# MinieasySens-RFM_V03-Build007.net
KiCad netlist of a schematic drawn in EAGLE
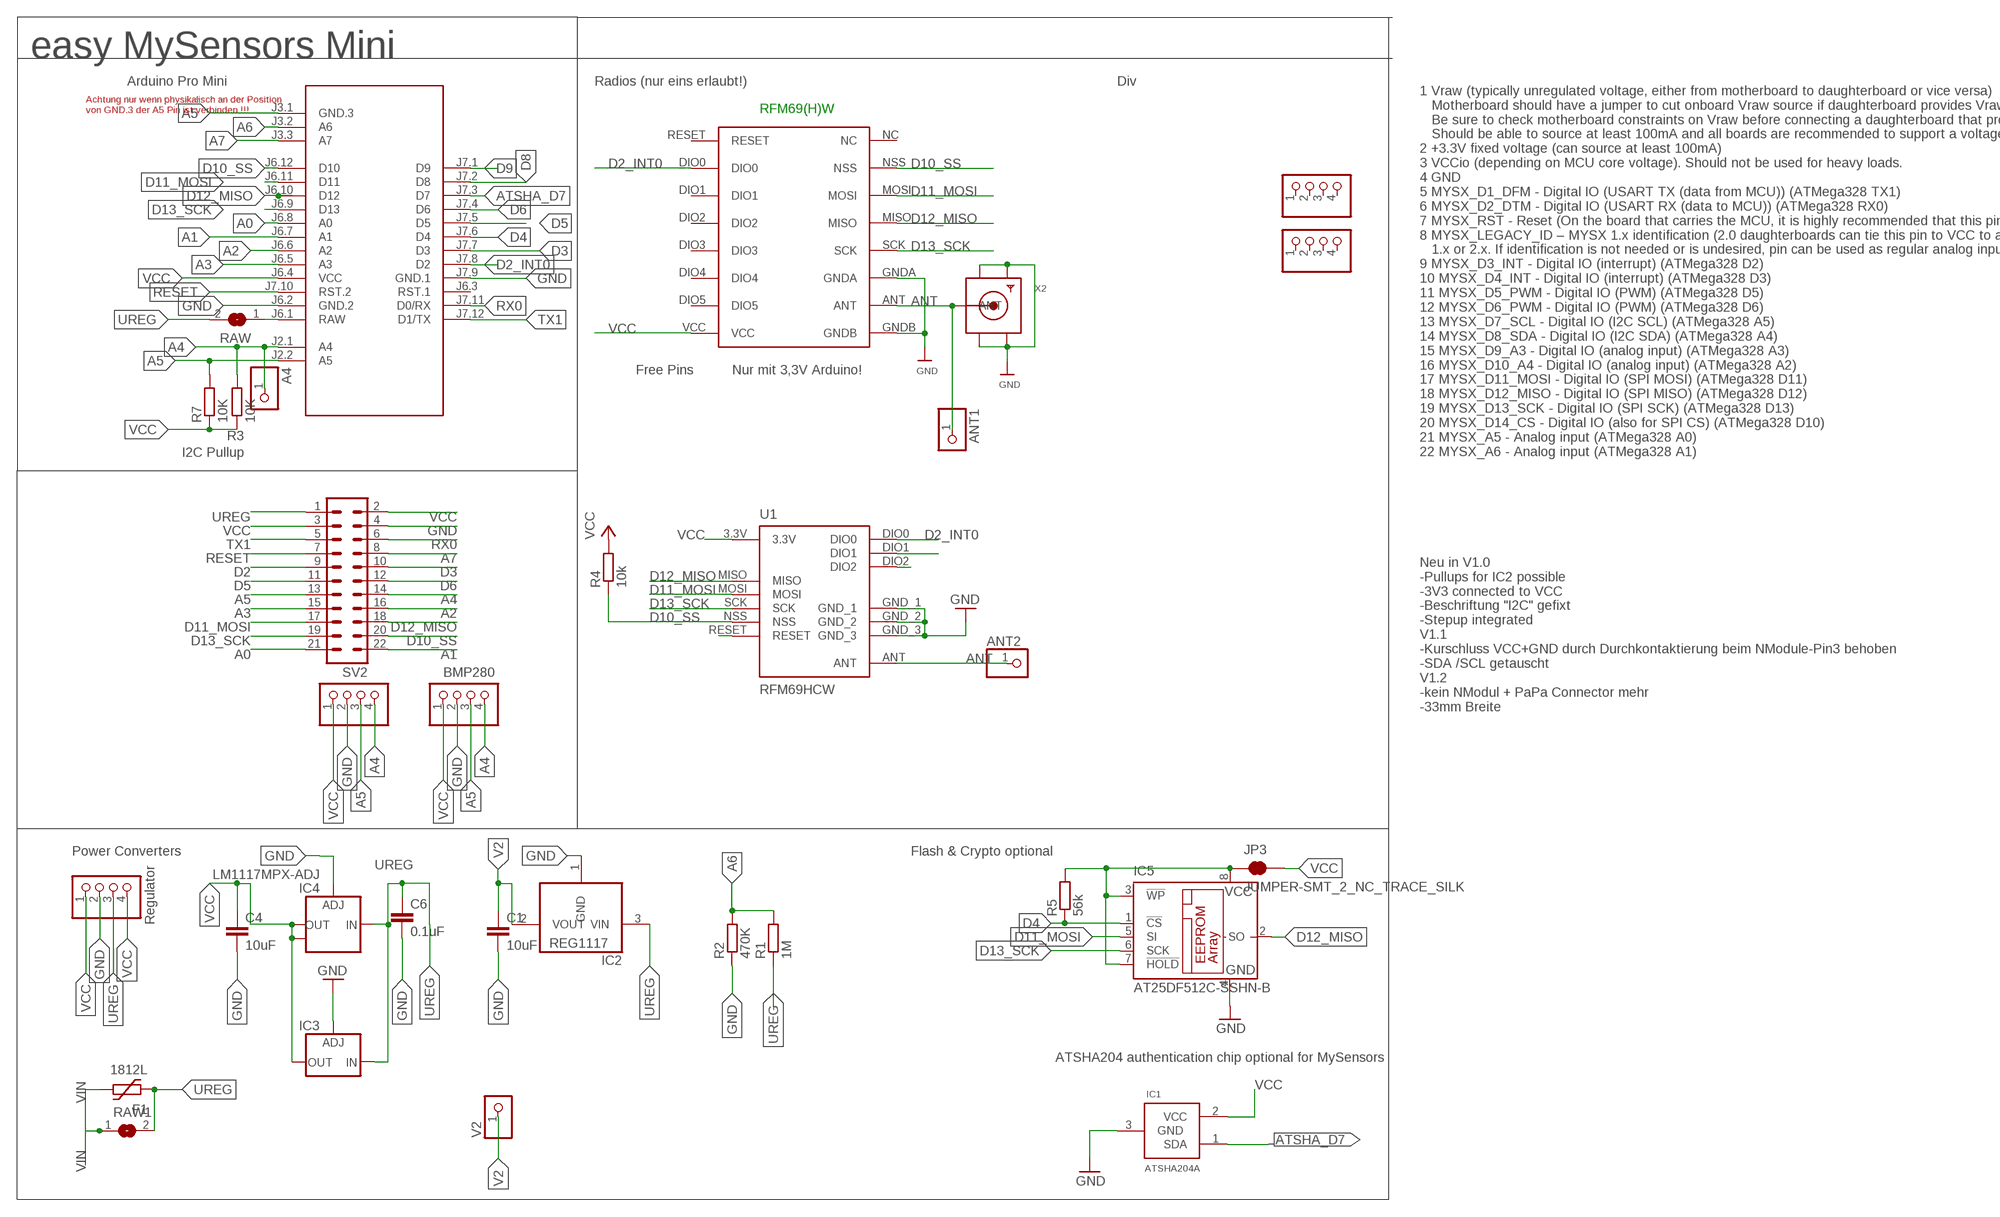
[diagram p0: schematic, sheet 1, part 1 of 2]
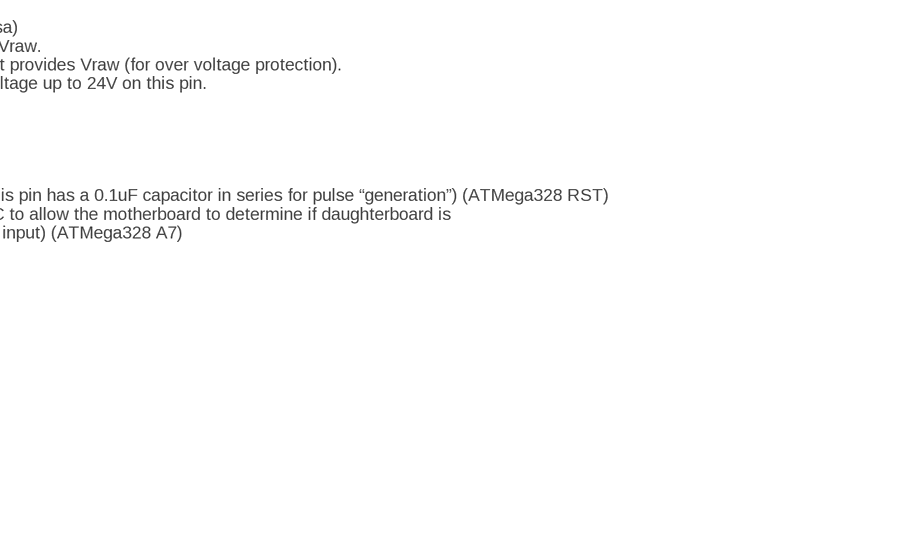
[diagram p1: schematic, sheet 1, part 2 of 2]

(export (version "E")
  (design (tool "Eeschema 10.0.6"))
  (components
    (comp (ref "A4")
      (value "PINHD-1X1")
      (footprint "eagle-import:1X01")
      (libsource (lib "eagle-import") (part "PINHD-1X1"))
    )
    (comp (ref "ANT1")
      (value "PINHD-1X1")
      (footprint "eagle-import:1X01")
      (libsource (lib "eagle-import") (part "PINHD-1X1"))
    )
    (comp (ref "ANT2")
      (value "PINHD-1X1")
      (footprint "eagle-import:1X01")
      (libsource (lib "eagle-import") (part "PINHD-1X1"))
    )
    (comp (ref "BH1750")
      (value "PINHD-1X04_2.54-S")
      (footprint "eagle-import:1X04-S")
      (libsource (lib "eagle-import") (part "PINHD-1X04_2.54-S"))
    )
    (comp (ref "C1")
      (value "10uF")
      (footprint "eagle-import:C1210")
      (libsource (lib "eagle-import") (part "C-EUC1210"))
    )
    (comp (ref "C4")
      (value "10uF")
      (footprint "eagle-import:C1210")
      (libsource (lib "eagle-import") (part "C-EUC1210"))
    )
    (comp (ref "C6")
      (value "0.1uF")
      (footprint "eagle-import:C1206")
      (libsource (lib "eagle-import") (part "C-EUC1206"))
    )
    (comp (ref "F1")
      (value "1812L")
      (footprint "eagle-import:1812L")
      (libsource (lib "eagle-import") (part "1812L"))
    )
    (comp (ref "I2C-1")
      (value "PINHD-1X04_2.54-S")
      (footprint "eagle-import:1X04-S")
      (libsource (lib "eagle-import") (part "PINHD-1X04_2.54-S"))
    )
    (comp (ref "IC1")
      (value "ATSHA204A")
      (footprint "eagle-import:SOT23")
      (libsource (lib "eagle-import") (part "ATSHA204A"))
    )
    (comp (ref "IC2")
      (value "REG1117")
      (footprint "eagle-import:SOT223")
      (libsource (lib "eagle-import") (part "REG1117"))
    )
    (comp (ref "IC3")
      (value "LD117ADT50TR")
      (footprint "eagle-import:DPACK")
      (libsource (lib "eagle-import") (part "LD117A?DT50TR"))
    )
    (comp (ref "IC4")
      (value "LM1117MPX-ADJ")
      (footprint "eagle-import:SOT223")
      (libsource (lib "eagle-import") (part "LM1117MPX-ADJ"))
    )
    (comp (ref "IC5")
      (value "AT25DF512C-SSHN-B")
      (footprint "eagle-import:SO-08")
      (fields (field (name "MF") "MICROCHIP") (field (name "MPN") "25AA080/SN"))
      (libsource (lib "eagle-import") (part "25SNAA080"))
    )
    (comp (ref "JP1")
      (value "PINHD-1X04_2.54-S")
      (footprint "eagle-import:1X04-S")
      (libsource (lib "eagle-import") (part "PINHD-1X04_2.54-S"))
    )
    (comp (ref "JP2")
      (value "PINHD-1X04_2.54-S")
      (footprint "eagle-import:1X04-S")
      (libsource (lib "eagle-import") (part "PINHD-1X04_2.54-S"))
    )
    (comp (ref "JP3")
      (value "JUMPER-SMT_2_NC_TRACE_SILK")
      (footprint "eagle-import:SMT-JUMPER_2_NC_TRACE_SILK")
      (libsource (lib "eagle-import") (part "JUMPER-SMT_2_NC_TRACE_SILK"))
    )
    (comp (ref "M1")
      (value "ARDUINO-PRO-MINI-3.3V#NP")
      (footprint "eagle-import:ARDUINO-PRO-MINI#NP")
      (libsource (lib "eagle-import") (part "ARDUINO-PRO-MINI-#NP3.3V"))
    )
    (comp (ref "R1")
      (value "1M")
      (footprint "eagle-import:R0805")
      (libsource (lib "eagle-import") (part "R-EU_R0805"))
    )
    (comp (ref "R2")
      (value "470K")
      (footprint "eagle-import:R0805")
      (libsource (lib "eagle-import") (part "R-EU_R0805"))
    )
    (comp (ref "R3")
      (value "10K")
      (footprint "eagle-import:R0805")
      (libsource (lib "eagle-import") (part "R-EU_R0805"))
    )
    (comp (ref "R4")
      (value "10k")
      (footprint "eagle-import:M0805")
      (libsource (lib "eagle-import") (part "R-EU_M0805"))
    )
    (comp (ref "R5")
      (value "56k")
      (footprint "eagle-import:M0805")
      (libsource (lib "eagle-import") (part "resistor_R-EU_M0805"))
    )
    (comp (ref "R7")
      (value "10K")
      (footprint "eagle-import:R0805")
      (libsource (lib "eagle-import") (part "R-EU_R0805"))
    )
    (comp (ref "RAW") (value "SJ") (footprint "eagle-import:SJ") (libsource (lib "eagle-import") (part "SJ")))
    (comp (ref "RAW1")
      (value "SJ")
      (footprint "eagle-import:SJ")
      (libsource (lib "eagle-import") (part "SJ"))
    )
    (comp (ref "RFM69W")
      (value "RFM69HW")
      (footprint "eagle-import:RFM")
      (libsource (lib "eagle-import") (part "RFM69HW"))
    )
    (comp (ref "STEPDWN")
      (value "PINHD-1X04_2.54-S")
      (footprint "eagle-import:1X04-S")
      (libsource (lib "eagle-import") (part "PINHD-1X04_2.54-S"))
    )
    (comp (ref "SV2")
      (value "MA11-2")
      (footprint "eagle-import:MA11-2")
      (libsource (lib "eagle-import") (part "MA11-2"))
    )
    (comp (ref "U1")
      (value "RFM69HCW")
      (footprint "eagle-import:RFM69HCW-XXXS2")
      (libsource (lib "eagle-import") (part "RFM69HCW"))
    )
    (comp (ref "V2")
      (value "PINHD-1X1")
      (footprint "eagle-import:1X01")
      (libsource (lib "eagle-import") (part "PINHD-1X1"))
    )
    (comp (ref "X2")
      (value "SMACONNECTOR_EDGE")
      (footprint "eagle-import:SMA_EDGELAUNCH")
      (libsource (lib "eagle-import") (part "SMACONNECTOR_EDGE"))
    )
  )
  (nets
    (net (code "1") (name "/ANT") (class "Default")
      (node (ref "ANT1") (pin "1") (pinfunction "1_1") (pintype "passive"))
      (node (ref "ANT2") (pin "1") (pinfunction "1_1") (pintype "passive"))
      (node (ref "RFM69W") (pin "ANT") (pinfunction "ANT_ANT") (pintype "bidirectional"))
      (node (ref "U1") (pin "ANT") (pinfunction "ANT_ANT") (pintype "passive"))
      (node (ref "X2") (pin "P") (pinfunction "ANT_P") (pintype "bidirectional"))
    )
    (net (code "2") (name "/D2") (class "Default")
      (node (ref "SV2") (pin "9") (pinfunction "9_9") (pintype "passive"))
    )
    (net (code "3") (name "/VIN") (class "Default")
      (node (ref "F1") (pin "P$2") (pinfunction "2_P$2") (pintype "passive"))
      (node (ref "RAW1") (pin "1") (pinfunction "1_1") (pintype "passive"))
    )
    (net (code "4") (name "A0") (class "Default")
      (node (ref "M1") (pin "J6.8") (pinfunction "A0_J6.8") (pintype "bidirectional"))
      (node (ref "SV2") (pin "21") (pinfunction "21_21") (pintype "passive"))
    )
    (net (code "5") (name "A1") (class "Default")
      (node (ref "M1") (pin "J6.7") (pinfunction "A1_J6.7") (pintype "bidirectional"))
      (node (ref "SV2") (pin "22") (pinfunction "22_22") (pintype "passive"))
    )
    (net (code "6") (name "A2") (class "Default")
      (node (ref "M1") (pin "J6.6") (pinfunction "A2_J6.6") (pintype "bidirectional"))
      (node (ref "SV2") (pin "16") (pinfunction "16_16") (pintype "passive"))
    )
    (net (code "7") (name "A3") (class "Default")
      (node (ref "M1") (pin "J6.5") (pinfunction "A3_J6.5") (pintype "bidirectional"))
      (node (ref "SV2") (pin "15") (pinfunction "15_15") (pintype "passive"))
    )
    (net (code "8") (name "A4") (class "Default")
      (node (ref "A4") (pin "1") (pinfunction "1_1") (pintype "passive"))
      (node (ref "BH1750") (pin "4") (pinfunction "4_4") (pintype "passive"))
      (node (ref "I2C-1") (pin "4") (pinfunction "4_4") (pintype "passive"))
      (node (ref "M1") (pin "J2.1") (pinfunction "A4_J2.1") (pintype "bidirectional"))
      (node (ref "R3") (pin "2") (pinfunction "2_2") (pintype "passive"))
      (node (ref "SV2") (pin "14") (pinfunction "14_14") (pintype "passive"))
    )
    (net (code "9") (name "A5") (class "Default")
      (node (ref "BH1750") (pin "3") (pinfunction "3_3") (pintype "passive"))
      (node (ref "I2C-1") (pin "3") (pinfunction "3_3") (pintype "passive"))
      (node (ref "M1") (pin "J2.2") (pinfunction "A5_J2.2") (pintype "bidirectional"))
      (node (ref "M1") (pin "J3.1") (pinfunction "GND.3_J3.1") (pintype "bidirectional"))
      (node (ref "R7") (pin "2") (pinfunction "2_2") (pintype "passive"))
      (node (ref "SV2") (pin "13") (pinfunction "13_13") (pintype "passive"))
    )
    (net (code "10") (name "A6") (class "Default")
      (node (ref "M1") (pin "J3.2") (pinfunction "A6_J3.2") (pintype "bidirectional"))
      (node (ref "R1") (pin "2") (pinfunction "2_2") (pintype "passive"))
      (node (ref "R2") (pin "2") (pinfunction "2_2") (pintype "passive"))
    )
    (net (code "11") (name "A7") (class "Default")
      (node (ref "M1") (pin "J3.3") (pinfunction "A7_J3.3") (pintype "bidirectional"))
      (node (ref "SV2") (pin "8") (pinfunction "8_8") (pintype "passive"))
    )
    (net (code "12") (name "ATSHA_D7") (class "Default")
      (node (ref "IC1") (pin "1") (pinfunction "SDA_1") (pintype "bidirectional"))
      (node (ref "M1") (pin "J7.3") (pinfunction "D7_J7.3") (pintype "bidirectional"))
    )
    (net (code "13") (name "D2_INT0") (class "Default")
      (node (ref "M1") (pin "J7.8") (pinfunction "D2_J7.8") (pintype "bidirectional"))
      (node (ref "RFM69W") (pin "DIO0") (pinfunction "DIO0_DIO0") (pintype "bidirectional"))
      (node (ref "U1") (pin "DIO0") (pinfunction "DIO0_DIO0") (pintype "bidirectional"))
    )
    (net (code "14") (name "D3") (class "Default")
      (node (ref "M1") (pin "J7.7") (pinfunction "D3_J7.7") (pintype "bidirectional"))
      (node (ref "SV2") (pin "10") (pinfunction "10_10") (pintype "passive"))
    )
    (net (code "15") (name "D4") (class "Default")
      (node (ref "IC5") (pin "1") (pinfunction "~{CS}_1") (pintype "input"))
      (node (ref "M1") (pin "J7.6") (pinfunction "D4_J7.6") (pintype "bidirectional"))
      (node (ref "R5") (pin "1") (pinfunction "1_1") (pintype "passive"))
    )
    (net (code "16") (name "D5") (class "Default")
      (node (ref "M1") (pin "J7.5") (pinfunction "D5_J7.5") (pintype "bidirectional"))
      (node (ref "SV2") (pin "11") (pinfunction "11_11") (pintype "passive"))
    )
    (net (code "17") (name "D6") (class "Default")
      (node (ref "M1") (pin "J7.4") (pinfunction "D6_J7.4") (pintype "bidirectional"))
      (node (ref "SV2") (pin "12") (pinfunction "12_12") (pintype "passive"))
    )
    (net (code "18") (name "D8") (class "Default")
      (node (ref "M1") (pin "J7.2") (pinfunction "D8_J7.2") (pintype "bidirectional"))
    )
    (net (code "19") (name "D9") (class "Default")
      (node (ref "M1") (pin "J7.1") (pinfunction "D9_J7.1") (pintype "bidirectional"))
    )
    (net (code "20") (name "D10_SS") (class "Default")
      (node (ref "M1") (pin "J6.12") (pinfunction "D10_J6.12") (pintype "bidirectional"))
      (node (ref "R4") (pin "1") (pinfunction "1_1") (pintype "passive"))
      (node (ref "RFM69W") (pin "NSS") (pinfunction "NSS_NSS") (pintype "bidirectional"))
      (node (ref "SV2") (pin "20") (pinfunction "20_20") (pintype "passive"))
      (node (ref "U1") (pin "NSS") (pinfunction "NSS_NSS") (pintype "input"))
    )
    (net (code "21") (name "D11_MOSI") (class "Default")
      (node (ref "IC5") (pin "5") (pinfunction "SI_5") (pintype "input"))
      (node (ref "M1") (pin "J6.11") (pinfunction "D11_J6.11") (pintype "bidirectional"))
      (node (ref "RFM69W") (pin "MOSI") (pinfunction "MOSI_MOSI") (pintype "bidirectional"))
      (node (ref "SV2") (pin "17") (pinfunction "17_17") (pintype "passive"))
      (node (ref "U1") (pin "MOSI") (pinfunction "MOSI_MOSI") (pintype "input"))
    )
    (net (code "22") (name "D12_MISO") (class "Default")
      (node (ref "IC5") (pin "2") (pinfunction "SO_2") (pintype "bidirectional"))
      (node (ref "M1") (pin "J6.10") (pinfunction "D12_J6.10") (pintype "bidirectional"))
      (node (ref "RFM69W") (pin "MISO") (pinfunction "MISO_MISO") (pintype "bidirectional"))
      (node (ref "SV2") (pin "18") (pinfunction "18_18") (pintype "passive"))
      (node (ref "U1") (pin "MISO") (pinfunction "MISO_MISO") (pintype "bidirectional"))
    )
    (net (code "23") (name "D13_SCK") (class "Default")
      (node (ref "IC5") (pin "6") (pinfunction "SCK_6") (pintype "input"))
      (node (ref "M1") (pin "J6.9") (pinfunction "D13_J6.9") (pintype "bidirectional"))
      (node (ref "RFM69W") (pin "SCK") (pinfunction "SCK_SCK") (pintype "bidirectional"))
      (node (ref "SV2") (pin "19") (pinfunction "19_19") (pintype "passive"))
      (node (ref "U1") (pin "SCK") (pinfunction "SCK_SCK") (pintype "input"))
    )
    (net (code "24") (name "GND") (class "Default")
      (node (ref "BH1750") (pin "2") (pinfunction "2_2") (pintype "passive"))
      (node (ref "C1") (pin "2") (pinfunction "2_2") (pintype "passive"))
      (node (ref "C4") (pin "2") (pinfunction "2_2") (pintype "passive"))
      (node (ref "C6") (pin "2") (pinfunction "2_2") (pintype "passive"))
      (node (ref "I2C-1") (pin "2") (pinfunction "2_2") (pintype "passive"))
      (node (ref "IC1") (pin "3") (pinfunction "GND_3") (pintype "bidirectional"))
      (node (ref "IC2") (pin "1") (pinfunction "GND_1") (pintype "power_in"))
      (node (ref "IC3") (pin "1") (pinfunction "ADJ_1") (pintype "input"))
      (node (ref "IC4") (pin "1") (pinfunction "ADJ_1") (pintype "input"))
      (node (ref "IC5") (pin "4") (pinfunction "GND_4") (pintype "power_in"))
      (node (ref "M1") (pin "J6.2") (pinfunction "GND.2_J6.2") (pintype "power_in"))
      (node (ref "M1") (pin "J7.9") (pinfunction "GND.1_J7.9") (pintype "power_in"))
      (node (ref "R2") (pin "1") (pinfunction "1_1") (pintype "passive"))
      (node (ref "RFM69W") (pin "GNDA") (pinfunction "GNDA_GNDA") (pintype "bidirectional"))
      (node (ref "RFM69W") (pin "GNDB") (pinfunction "GNDB_GNDB") (pintype "bidirectional"))
      (node (ref "STEPDWN") (pin "2") (pinfunction "2_2") (pintype "passive"))
      (node (ref "SV2") (pin "4") (pinfunction "4_4") (pintype "passive"))
      (node (ref "U1") (pin "GND_1") (pinfunction "GND_1_GND_1") (pintype "power_in"))
      (node (ref "U1") (pin "GND_2") (pinfunction "GND_2_GND_2") (pintype "power_in"))
      (node (ref "U1") (pin "GND_3") (pinfunction "GND_3_GND_3") (pintype "power_in"))
      (node (ref "X2") (pin "GND@1") (pinfunction "GND4_GND@1") (pintype "power_in"))
      (node (ref "X2") (pin "GND@2") (pinfunction "GND3_GND@2") (pintype "power_in"))
      (node (ref "X2") (pin "GND@3") (pinfunction "GND2_GND@3") (pintype "power_in"))
      (node (ref "X2") (pin "GND@4") (pinfunction "GND1_GND@4") (pintype "power_in"))
    )
    (net (code "25") (name "Net-(IC5-VCC)") (class "Default")
      (node (ref "IC5") (pin "3") (pinfunction "~{WP}_3") (pintype "input"))
      (node (ref "IC5") (pin "7") (pinfunction "~{HOLD}_7") (pintype "input"))
      (node (ref "IC5") (pin "8") (pinfunction "VCC_8") (pintype "power_in"))
      (node (ref "JP3") (pin "1") (pinfunction "1_1") (pintype "passive"))
      (node (ref "R5") (pin "2") (pinfunction "2_2") (pintype "passive"))
    )
    (net (code "26") (name "Net-(M1-RAW)") (class "Default")
      (node (ref "M1") (pin "J6.1") (pinfunction "RAW_J6.1") (pintype "power_in"))
      (node (ref "RAW") (pin "1") (pinfunction "1_1") (pintype "passive"))
    )
    (net (code "27") (name "RESET") (class "Default")
      (node (ref "M1") (pin "J7.10") (pinfunction "RST.2_J7.10") (pintype "bidirectional"))
      (node (ref "SV2") (pin "7") (pinfunction "7_7") (pintype "passive"))
    )
    (net (code "28") (name "RX0") (class "Default")
      (node (ref "M1") (pin "J7.11") (pinfunction "D0/RX_J7.11") (pintype "bidirectional"))
      (node (ref "SV2") (pin "6") (pinfunction "6_6") (pintype "passive"))
    )
    (net (code "29") (name "TX1") (class "Default")
      (node (ref "M1") (pin "J7.12") (pinfunction "D1/TX_J7.12") (pintype "bidirectional"))
      (node (ref "SV2") (pin "5") (pinfunction "5_5") (pintype "passive"))
    )
    (net (code "30") (name "UREG") (class "Default")
      (node (ref "C6") (pin "1") (pinfunction "1_1") (pintype "passive"))
      (node (ref "F1") (pin "P$1") (pinfunction "1_P$1") (pintype "passive"))
      (node (ref "IC2") (pin "3") (pinfunction "VIN_3") (pintype "input"))
      (node (ref "IC3") (pin "3") (pinfunction "IN_3") (pintype "input"))
      (node (ref "IC4") (pin "3") (pinfunction "IN_3") (pintype "input"))
      (node (ref "R1") (pin "1") (pinfunction "1_1") (pintype "passive"))
      (node (ref "RAW") (pin "2") (pinfunction "2_2") (pintype "passive"))
      (node (ref "RAW1") (pin "2") (pinfunction "2_2") (pintype "passive"))
      (node (ref "STEPDWN") (pin "3") (pinfunction "3_3") (pintype "passive"))
      (node (ref "SV2") (pin "1") (pinfunction "1_1") (pintype "passive"))
    )
    (net (code "31") (name "V2") (class "Default")
      (node (ref "C1") (pin "1") (pinfunction "1_1") (pintype "passive"))
      (node (ref "IC2") (pin "2") (pinfunction "VOUT_2") (pintype "output"))
      (node (ref "V2") (pin "1") (pinfunction "1_1") (pintype "passive"))
    )
    (net (code "32") (name "VCC") (class "Default")
      (node (ref "BH1750") (pin "1") (pinfunction "1_1") (pintype "passive"))
      (node (ref "C4") (pin "1") (pinfunction "1_1") (pintype "passive"))
      (node (ref "I2C-1") (pin "1") (pinfunction "1_1") (pintype "passive"))
      (node (ref "IC1") (pin "2") (pinfunction "VCC_2") (pintype "bidirectional"))
      (node (ref "IC3") (pin "4") (pinfunction "OUT_4") (pintype "passive"))
      (node (ref "IC4") (pin "2") (pinfunction "OUT_2") (pintype "passive"))
      (node (ref "IC4") (pin "TAB") (pinfunction "OUT1_TAB") (pintype "passive"))
      (node (ref "JP3") (pin "2") (pinfunction "2_2") (pintype "passive"))
      (node (ref "M1") (pin "J6.4") (pinfunction "VCC_J6.4") (pintype "power_in"))
      (node (ref "R3") (pin "1") (pinfunction "1_1") (pintype "passive"))
      (node (ref "R4") (pin "2") (pinfunction "2_2") (pintype "passive"))
      (node (ref "R7") (pin "1") (pinfunction "1_1") (pintype "passive"))
      (node (ref "RFM69W") (pin "VCC") (pinfunction "VCC_VCC") (pintype "bidirectional"))
      (node (ref "STEPDWN") (pin "1") (pinfunction "1_1") (pintype "passive"))
      (node (ref "STEPDWN") (pin "4") (pinfunction "4_4") (pintype "passive"))
      (node (ref "SV2") (pin "2") (pinfunction "2_2") (pintype "passive"))
      (node (ref "SV2") (pin "3") (pinfunction "3_3") (pintype "passive"))
      (node (ref "U1") (pin "3.3V") (pinfunction "3.3V_3.3V") (pintype "power_in"))
    )
    (net (code "33") (name "unconnected-(JP1-Pad1)") (class "Default")
      (node (ref "JP1") (pin "1") (pinfunction "1_1") (pintype "passive"))
    )
    (net (code "34") (name "unconnected-(JP1-Pad2)") (class "Default")
      (node (ref "JP1") (pin "2") (pinfunction "2_2") (pintype "passive"))
    )
    (net (code "35") (name "unconnected-(JP1-Pad3)") (class "Default")
      (node (ref "JP1") (pin "3") (pinfunction "3_3") (pintype "passive"))
    )
    (net (code "36") (name "unconnected-(JP1-Pad4)") (class "Default")
      (node (ref "JP1") (pin "4") (pinfunction "4_4") (pintype "passive"))
    )
    (net (code "37") (name "unconnected-(JP2-Pad1)") (class "Default")
      (node (ref "JP2") (pin "1") (pinfunction "1_1") (pintype "passive"))
    )
    (net (code "38") (name "unconnected-(JP2-Pad2)") (class "Default")
      (node (ref "JP2") (pin "2") (pinfunction "2_2") (pintype "passive"))
    )
    (net (code "39") (name "unconnected-(JP2-Pad3)") (class "Default")
      (node (ref "JP2") (pin "3") (pinfunction "3_3") (pintype "passive"))
    )
    (net (code "40") (name "unconnected-(JP2-Pad4)") (class "Default")
      (node (ref "JP2") (pin "4") (pinfunction "4_4") (pintype "passive"))
    )
    (net (code "41") (name "unconnected-(M1-RST.1-PadJ6.3)") (class "Default")
      (node (ref "M1") (pin "J6.3") (pinfunction "RST.1_J6.3") (pintype "bidirectional"))
    )
    (net (code "42") (name "unconnected-(RFM69W-PadDIO1)") (class "Default")
      (node (ref "RFM69W") (pin "DIO1") (pinfunction "DIO1_DIO1") (pintype "bidirectional"))
    )
    (net (code "43") (name "unconnected-(RFM69W-PadDIO2)") (class "Default")
      (node (ref "RFM69W") (pin "DIO2") (pinfunction "DIO2_DIO2") (pintype "bidirectional"))
    )
    (net (code "44") (name "unconnected-(RFM69W-PadDIO3)") (class "Default")
      (node (ref "RFM69W") (pin "DIO3") (pinfunction "DIO3_DIO3") (pintype "bidirectional"))
    )
    (net (code "45") (name "unconnected-(RFM69W-PadDIO4)") (class "Default")
      (node (ref "RFM69W") (pin "DIO4") (pinfunction "DIO4_DIO4") (pintype "bidirectional"))
    )
    (net (code "46") (name "unconnected-(RFM69W-PadDIO5)") (class "Default")
      (node (ref "RFM69W") (pin "DIO5") (pinfunction "DIO5_DIO5") (pintype "bidirectional"))
    )
    (net (code "47") (name "unconnected-(RFM69W-PadNC)") (class "Default")
      (node (ref "RFM69W") (pin "NC") (pinfunction "NC_NC") (pintype "bidirectional"))
    )
    (net (code "48") (name "unconnected-(RFM69W-PadRESET)") (class "Default")
      (node (ref "RFM69W") (pin "RESET") (pinfunction "RESET_RESET") (pintype "bidirectional"))
    )
    (net (code "49") (name "unconnected-(U1-PadDIO1)") (class "Default")
      (node (ref "U1") (pin "DIO1") (pinfunction "DIO1_DIO1") (pintype "bidirectional"))
    )
    (net (code "50") (name "unconnected-(U1-PadDIO2)") (class "Default")
      (node (ref "U1") (pin "DIO2") (pinfunction "DIO2_DIO2") (pintype "bidirectional"))
    )
    (net (code "51") (name "unconnected-(U1-PadRESET)") (class "Default")
      (node (ref "U1") (pin "RESET") (pinfunction "RESET_RESET") (pintype "input"))
    )
  )
)
